# 2_ADSTM32_MCU.net
KiCad netlist of a schematic drawn in Altium Designer
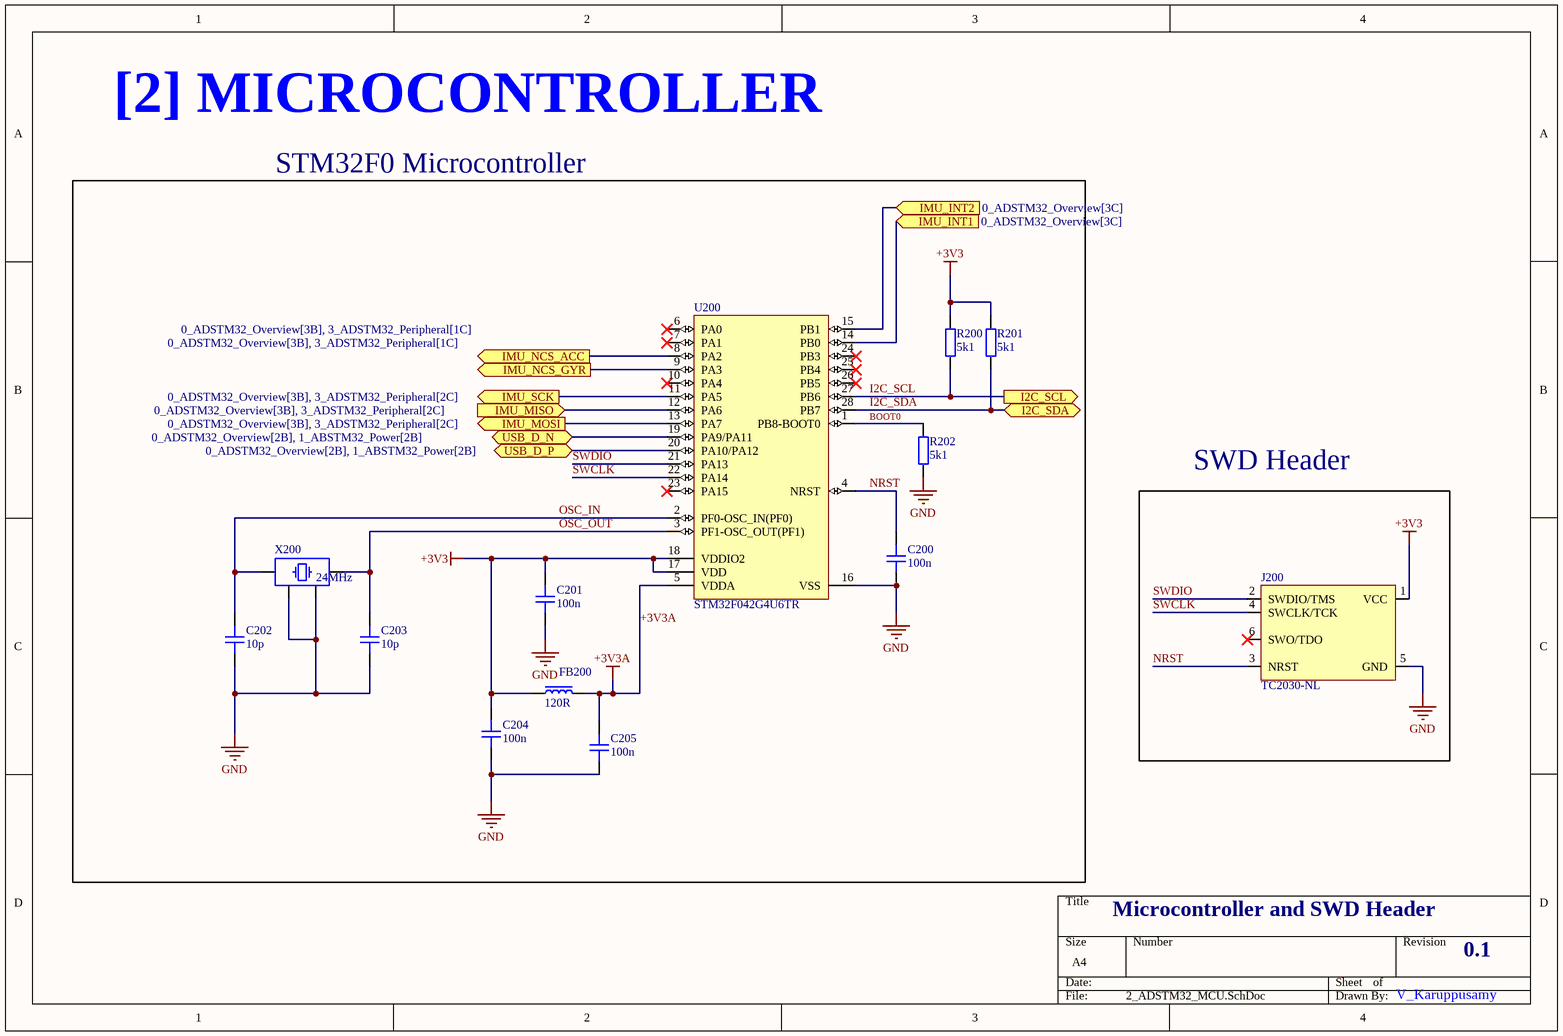
[diagram p0: 2_ADSTM32_MCU.SchDoc]

(export (version "E")
  (design (tool "Eeschema 10.0.6"))
  (components
    (comp (ref "C200")
      (value "100n")
      (footprint "CAP_0805")
      (description "Capacitor SMD 0805 16V")
      (libsource (lib "Schematic-Lib-PhilsLab") (part "CAP_0805_16V"))
    )
    (comp (ref "C201")
      (value "100n")
      (footprint "CAP_0805")
      (description "Capacitor SMD 0805 16V")
      (libsource (lib "Schematic-Lib-PhilsLab") (part "CAP_0805_16V"))
    )
    (comp (ref "C202")
      (value "10p")
      (footprint "CAP_0805")
      (description "Capacitor SMD 0805 16V")
      (libsource (lib "Schematic-Lib-PhilsLab") (part "CAP_0805_16V"))
    )
    (comp (ref "C203")
      (value "10p")
      (footprint "CAP_0805")
      (description "Capacitor SMD 0805 16V")
      (libsource (lib "Schematic-Lib-PhilsLab") (part "CAP_0805_16V"))
    )
    (comp (ref "C204")
      (value "100n")
      (footprint "CAP_0805")
      (description "Capacitor SMD 0805 16V")
      (libsource (lib "Schematic-Lib-PhilsLab") (part "CAP_0805_16V"))
    )
    (comp (ref "C205")
      (value "100n")
      (footprint "CAP_0805")
      (description "Capacitor SMD 0805 16V")
      (libsource (lib "Schematic-Lib-PhilsLab") (part "CAP_0805_16V"))
    )
    (comp (ref "FB200")
      (value "120R")
      (footprint "FB_0402")
      (description "Ferrite Bead SMD 0402")
      (libsource (lib "Schematic-Lib-PhilsLab") (part "FB_0402"))
    )
    (comp (ref "J200")
      (value "TC2030-NL")
      (footprint "TC2030-NL-FP")
      (description "Tag-Connect No-Solder SWD Debug Connector (No Legs) DO NOT PLACE")
      (fields
        (field (name "MANUFACTURER") "Tag-Connect")
        (field (name "MANUFACTURER PART NUMBER") "TC2030-NL-FP")
      )
      (libsource (lib "Schematic-Lib-PhilsLab") (part "TC2030-NL"))
    )
    (comp (ref "R200")
      (value "5k1")
      (footprint "RES_0603")
      (description "Resistor SMD 0603")
      (libsource (lib "Schematic-Lib-PhilsLab") (part "RES_0603"))
    )
    (comp (ref "R201")
      (value "5k1")
      (footprint "RES_0603")
      (description "Resistor SMD 0603")
      (libsource (lib "Schematic-Lib-PhilsLab") (part "RES_0603"))
    )
    (comp (ref "R202")
      (value "5k1")
      (footprint "RES_0603")
      (description "Resistor SMD 0603")
      (libsource (lib "Schematic-Lib-PhilsLab") (part "RES_0603"))
    )
    (comp (ref "U200")
      (value "STM32F042G4U6TR")
      (footprint "STM-UFQFPN28_V")
      (fields (field (name "MANUFACTURER") "STMicroelectronics"))
      (libsource (lib "Altium Content Vault") (part "MC-ARM-STM32F042-UFQFPN28"))
    )
    (comp (ref "X200")
      (value "24MHz")
      (footprint "XTAL_3225")
      (description "Crystal SMD 24MHz 10PPM 7pF 3225")
      (fields (field (name "MANUFACTURER") "Epson"))
      (libsource (lib "Schematic-Lib-PhilsLab") (part "TSX-3225_24.0000MF15X-AC"))
    )
  )
  (nets
    (net (code "1") (name "+3V3") (class "Default")
      (node (ref "C201") (pin "2") (pinfunction "2_2") (pintype "passive"))
      (node (ref "C204") (pin "2") (pinfunction "2_2") (pintype "passive"))
      (node (ref "FB200") (pin "1") (pinfunction "1_1") (pintype "passive"))
      (node (ref "J200") (pin "1") (pinfunction "VCC_1") (pintype "passive"))
      (node (ref "R200") (pin "2") (pinfunction "2_2") (pintype "passive"))
      (node (ref "R201") (pin "2") (pinfunction "2_2") (pintype "passive"))
      (node (ref "U200") (pin "17") (pinfunction "VDD_17") (pintype "power_in"))
      (node (ref "U200") (pin "18") (pinfunction "VDDIO2_18") (pintype "power_in"))
    )
    (net (code "2") (name "+3V3A") (class "Default")
      (node (ref "C205") (pin "2") (pinfunction "2_2") (pintype "passive"))
      (node (ref "FB200") (pin "2") (pinfunction "2_2") (pintype "passive"))
      (node (ref "U200") (pin "5") (pinfunction "VDDA_5") (pintype "power_in"))
    )
    (net (code "3") (name "/BOOT0") (class "Default")
      (node (ref "R202") (pin "2") (pinfunction "2_2") (pintype "passive"))
      (node (ref "U200") (pin "1") (pinfunction "PB8-BOOT0_1") (pintype "bidirectional"))
    )
    (net (code "4") (name "/I2C_SCL") (class "Default")
      (node (ref "R200") (pin "1") (pinfunction "1_1") (pintype "passive"))
      (node (ref "U200") (pin "27") (pinfunction "PB6_27") (pintype "bidirectional"))
    )
    (net (code "5") (name "/I2C_SDA") (class "Default")
      (node (ref "R201") (pin "1") (pinfunction "1_1") (pintype "passive"))
      (node (ref "U200") (pin "28") (pinfunction "PB7_28") (pintype "bidirectional"))
    )
    (net (code "6") (name "/IMU_INT1") (class "Default")
      (node (ref "U200") (pin "14") (pinfunction "PB0_14") (pintype "bidirectional"))
    )
    (net (code "7") (name "/IMU_INT2") (class "Default")
      (node (ref "U200") (pin "15") (pinfunction "PB1_15") (pintype "bidirectional"))
    )
    (net (code "8") (name "/IMU_MISO") (class "Default")
      (node (ref "U200") (pin "12") (pinfunction "PA6_12") (pintype "bidirectional"))
    )
    (net (code "9") (name "/IMU_MOSI") (class "Default")
      (node (ref "U200") (pin "13") (pinfunction "PA7_13") (pintype "bidirectional"))
    )
    (net (code "10") (name "/IMU_NCS_ACC") (class "Default")
      (node (ref "U200") (pin "8") (pinfunction "PA2_8") (pintype "bidirectional"))
    )
    (net (code "11") (name "/IMU_NCS_GYR") (class "Default")
      (node (ref "U200") (pin "9") (pinfunction "PA3_9") (pintype "bidirectional"))
    )
    (net (code "12") (name "/IMU_SCK") (class "Default")
      (node (ref "U200") (pin "11") (pinfunction "PA5_11") (pintype "bidirectional"))
    )
    (net (code "13") (name "/NRST") (class "Default")
      (node (ref "C200") (pin "2") (pinfunction "2_2") (pintype "passive"))
      (node (ref "J200") (pin "3") (pinfunction "NRST_3") (pintype "passive"))
      (node (ref "U200") (pin "4") (pinfunction "NRST_4") (pintype "bidirectional"))
    )
    (net (code "14") (name "/OSC_IN") (class "Default")
      (node (ref "C202") (pin "2") (pinfunction "2_2") (pintype "passive"))
      (node (ref "U200") (pin "2") (pinfunction "PF0-OSC_IN(PF0)_2") (pintype "bidirectional"))
      (node (ref "X200") (pin "1") (pinfunction "1_1") (pintype "passive"))
    )
    (net (code "15") (name "/OSC_OUT") (class "Default")
      (node (ref "C203") (pin "2") (pinfunction "2_2") (pintype "passive"))
      (node (ref "U200") (pin "3") (pinfunction "PF1-OSC_OUT(PF1)_3") (pintype "bidirectional"))
      (node (ref "X200") (pin "3") (pinfunction "3_3") (pintype "passive"))
    )
    (net (code "16") (name "/SWCLK") (class "Default")
      (node (ref "J200") (pin "4") (pinfunction "SWCLK/TCK_4") (pintype "passive"))
      (node (ref "U200") (pin "22") (pinfunction "PA14_22") (pintype "bidirectional"))
    )
    (net (code "17") (name "/SWDIO") (class "Default")
      (node (ref "J200") (pin "2") (pinfunction "SWDIO/TMS_2") (pintype "passive"))
      (node (ref "U200") (pin "21") (pinfunction "PA13_21") (pintype "bidirectional"))
    )
    (net (code "18") (name "/USB_D_N") (class "Default")
      (node (ref "U200") (pin "19") (pinfunction "PA9/PA11_19") (pintype "bidirectional"))
    )
    (net (code "19") (name "/USB_D_P") (class "Default")
      (node (ref "U200") (pin "20") (pinfunction "PA10/PA12_20") (pintype "bidirectional"))
    )
    (net (code "20") (name "GND") (class "Default")
      (node (ref "C200") (pin "1") (pinfunction "1_1") (pintype "passive"))
      (node (ref "C201") (pin "1") (pinfunction "1_1") (pintype "passive"))
      (node (ref "C202") (pin "1") (pinfunction "1_1") (pintype "passive"))
      (node (ref "C203") (pin "1") (pinfunction "1_1") (pintype "passive"))
      (node (ref "C204") (pin "1") (pinfunction "1_1") (pintype "passive"))
      (node (ref "C205") (pin "1") (pinfunction "1_1") (pintype "passive"))
      (node (ref "J200") (pin "5") (pinfunction "GND_5") (pintype "passive"))
      (node (ref "R202") (pin "1") (pinfunction "1_1") (pintype "passive"))
      (node (ref "U200") (pin "16") (pinfunction "VSS_16") (pintype "power_in"))
      (node (ref "X200") (pin "2") (pinfunction "2_2") (pintype "passive"))
      (node (ref "X200") (pin "4") (pinfunction "4_4") (pintype "passive"))
    )
    (net (code "21") (name "unconnected-(J200-SWO{slash}TDO-Pad6)") (class "Default")
      (node (ref "J200") (pin "6") (pinfunction "SWO/TDO_6") (pintype "passive+no_connect"))
    )
    (net (code "22") (name "unconnected-(U200-PA0-Pad6)") (class "Default")
      (node (ref "U200") (pin "6") (pinfunction "PA0_6") (pintype "bidirectional+no_connect"))
    )
    (net (code "23") (name "unconnected-(U200-PA1-Pad7)") (class "Default")
      (node (ref "U200") (pin "7") (pinfunction "PA1_7") (pintype "bidirectional+no_connect"))
    )
    (net (code "24") (name "unconnected-(U200-PA4-Pad10)") (class "Default")
      (node (ref "U200") (pin "10") (pinfunction "PA4_10") (pintype "bidirectional+no_connect"))
    )
    (net (code "25") (name "unconnected-(U200-PA15-Pad23)") (class "Default")
      (node (ref "U200") (pin "23") (pinfunction "PA15_23") (pintype "bidirectional+no_connect"))
    )
    (net (code "26") (name "unconnected-(U200-PB3-Pad24)") (class "Default")
      (node (ref "U200") (pin "24") (pinfunction "PB3_24") (pintype "bidirectional+no_connect"))
    )
    (net (code "27") (name "unconnected-(U200-PB4-Pad25)") (class "Default")
      (node (ref "U200") (pin "25") (pinfunction "PB4_25") (pintype "bidirectional+no_connect"))
    )
    (net (code "28") (name "unconnected-(U200-PB5-Pad26)") (class "Default")
      (node (ref "U200") (pin "26") (pinfunction "PB5_26") (pintype "bidirectional+no_connect"))
    )
  )
)
